# Sheet1.net
KiCad netlist of a schematic drawn in Altium Designer
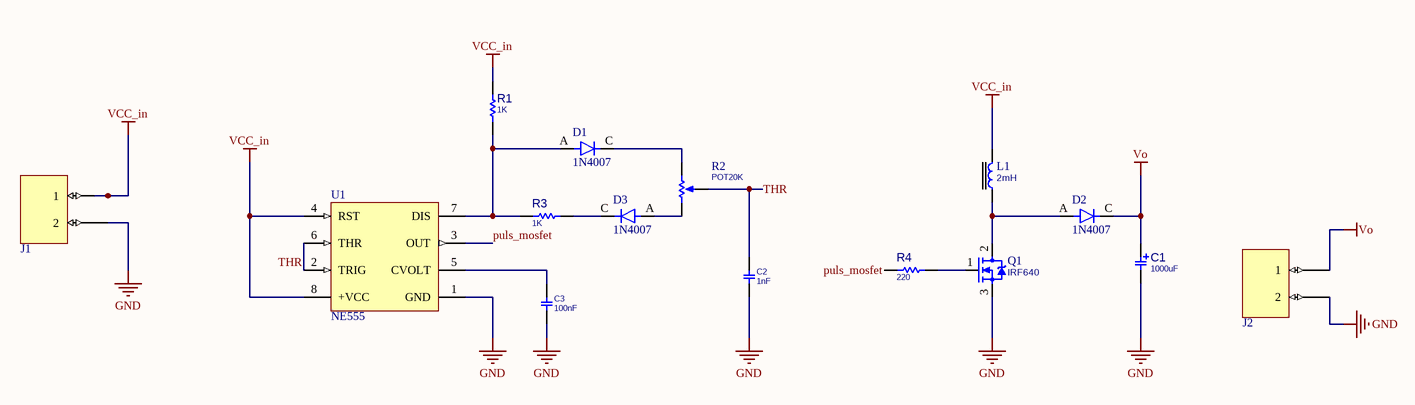
[diagram p0: Sheet1.SchDoc]

(export (version "E")
  (design (tool "Eeschema 10.0.6"))
  (components
    (comp (ref "C1")
      (value "1000uF")
      (footprint "C_EL_8X12")
      (description "CAP, THD, ELEC,")
      (fields (field (name "MANF_P#") "MANF_PART#") (field (name "MANF") "MANF"))
      (libsource (lib "passive_thd") (part "CAP_THD_EL_10X20"))
    )
    (comp (ref "C2")
      (value "1nF")
      (footprint "C_CER_D3")
      (description "CAP, THD, CER MULTI LAYER,")
      (fields (field (name "MANF_P#") "MANF_PART#") (field (name "MANF") "MANF"))
      (libsource (lib "passive_thd") (part "CAP_THD_CERML"))
    )
    (comp (ref "C3")
      (value "100nF")
      (footprint "C_CER_D3")
      (description "CAP, THD, CER MULTI LAYER,")
      (fields (field (name "MANF_P#") "MANF_PART#") (field (name "MANF") "MANF"))
      (libsource (lib "passive_thd") (part "CAP_THD_CERML"))
    )
    (comp (ref "D1")
      (value "1N4007")
      (footprint "DIOAD1060W80L520D270")
      (description "Diode Standard 1000 V 1A Through Hole DO-41")
      (fields (field (name "MF") "NTE Electronics, Inc."))
      (libsource (lib "1N4007") (part "1N4007"))
    )
    (comp (ref "D2")
      (value "1N4007")
      (footprint "DIOAD1060W80L520D270")
      (description "Diode Standard 1000 V 1A Through Hole DO-41")
      (fields (field (name "MF") "NTE Electronics, Inc."))
      (libsource (lib "1N4007") (part "1N4007"))
    )
    (comp (ref "D3")
      (value "1N4007")
      (footprint "DIOAD1060W80L520D270")
      (description "Diode Standard 1000 V 1A Through Hole DO-41")
      (fields (field (name "MF") "NTE Electronics, Inc."))
      (libsource (lib "1N4007") (part "1N4007"))
    )
    (comp (ref "J1")
      (value "con_x2")
      (footprint "TBG_2")
      (libsource (lib "My_liberary_Schematic") (part "con_x2"))
    )
    (comp (ref "J2")
      (value "con_x2")
      (footprint "TBG_2")
      (libsource (lib "My_liberary_Schematic") (part "con_x2"))
    )
    (comp (ref "L1")
      (value "2mH")
      (footprint "C_EL_10X20")
      (description "INDUCTOR, THD")
      (libsource (lib "passive_thd") (part "IND_THD"))
    )
    (comp (ref "Q1")
      (value "IRF640")
      (footprint "TO220_3")
      (description "MOSFET, N-CH, 0.15RDS, 18A, 300VDS, 2~4VGSth")
      (fields (field (name "MANF") "VISHAY, ON"))
      (libsource (lib "transistor_fet") (part "MOSN_IRF640_TO220"))
    )
    (comp (ref "R1")
      (value "1K")
      (footprint "R025W_AX04")
      (description "RESISTOR, THD")
      (fields (field (name "MANF_P#") "RK73H1ETTP4701F") (field (name "MANF") "KOA SPEER"))
      (libsource (lib "passive_thd") (part "RES_THD"))
    )
    (comp (ref "R2")
      (value "POT20K")
      (footprint "POT_7X5")
      (description "RESISTOR, THD, Potentiometer Volume")
      (libsource (lib "resistor_pot_trimmer") (part "RES_THD_POT_VOLUME"))
    )
    (comp (ref "R3")
      (value "1K")
      (footprint "R025W_AX04")
      (description "RESISTOR, THD")
      (fields (field (name "MANF_P#") "RK73H1ETTP4701F") (field (name "MANF") "KOA SPEER"))
      (libsource (lib "passive_thd") (part "RES_THD"))
    )
    (comp (ref "R4")
      (value "220")
      (footprint "R025W_AX04")
      (description "RESISTOR, THD")
      (fields (field (name "MANF_P#") "RK73H1ETTP4701F") (field (name "MANF") "KOA SPEER"))
      (libsource (lib "passive_thd") (part "RES_THD"))
    )
    (comp (ref "U1") (value "NE555") (footprint "NE555") (libsource (lib "NE555") (part "NE555")))
  )
  (nets
    (net (code "1") (name "/THR") (class "Default")
      (node (ref "C2") (pin "2") (pinfunction "2_2") (pintype "passive"))
      (node (ref "R2") (pin "2") (pinfunction "TAP_2") (pintype "passive"))
      (node (ref "U1") (pin "2") (pinfunction "TRIG_2") (pintype "input"))
      (node (ref "U1") (pin "6") (pinfunction "THR_6") (pintype "input"))
    )
    (net (code "2") (name "/puls_mosfet") (class "Default")
      (node (ref "R4") (pin "2") (pinfunction "2_2") (pintype "passive"))
      (node (ref "U1") (pin "3") (pinfunction "OUT_3") (pintype "output"))
    )
    (net (code "3") (name "GND") (class "Default")
      (node (ref "C1") (pin "2") (pinfunction "2_2") (pintype "passive"))
      (node (ref "C2") (pin "1") (pinfunction "1_1") (pintype "passive"))
      (node (ref "C3") (pin "1") (pinfunction "1_1") (pintype "passive"))
      (node (ref "J1") (pin "2") (pinfunction "2_2") (pintype "bidirectional"))
      (node (ref "J2") (pin "2") (pinfunction "2_2") (pintype "bidirectional"))
      (node (ref "Q1") (pin "3") (pinfunction "S_3") (pintype "passive"))
      (node (ref "U1") (pin "1") (pinfunction "GND_1") (pintype "power_in"))
    )
    (net (code "4") (name "Net-(D3-PadC)") (class "Default")
      (node (ref "D3") (pin "C") (pinfunction "C_C") (pintype "passive"))
      (node (ref "R3") (pin "1") (pinfunction "1_1") (pintype "passive"))
    )
    (net (code "5") (name "Net-(Q1-D)") (class "Default")
      (node (ref "D2") (pin "A") (pinfunction "A_A") (pintype "passive"))
      (node (ref "L1") (pin "1") (pinfunction "1_1") (pintype "passive"))
      (node (ref "Q1") (pin "2") (pinfunction "D_2") (pintype "passive"))
    )
    (net (code "6") (name "Net-(Q1-G)") (class "Default")
      (node (ref "Q1") (pin "1") (pinfunction "G_1") (pintype "passive"))
      (node (ref "R4") (pin "1") (pinfunction "1_1") (pintype "passive"))
    )
    (net (code "7") (name "Net-(R2-BOT)") (class "Default")
      (node (ref "D1") (pin "C") (pinfunction "C_C") (pintype "passive"))
      (node (ref "R2") (pin "3") (pinfunction "BOT_3") (pintype "passive"))
    )
    (net (code "8") (name "Net-(R2-TOP)") (class "Default")
      (node (ref "D3") (pin "A") (pinfunction "A_A") (pintype "passive"))
      (node (ref "R2") (pin "1") (pinfunction "TOP_1") (pintype "passive"))
    )
    (net (code "9") (name "Net-(U1-CVOLT)") (class "Default")
      (node (ref "C3") (pin "2") (pinfunction "2_2") (pintype "passive"))
      (node (ref "U1") (pin "5") (pinfunction "CVOLT_5") (pintype "passive"))
    )
    (net (code "10") (name "Net-(U1-DIS)") (class "Default")
      (node (ref "D1") (pin "A") (pinfunction "A_A") (pintype "passive"))
      (node (ref "R1") (pin "1") (pinfunction "1_1") (pintype "passive"))
      (node (ref "R3") (pin "2") (pinfunction "2_2") (pintype "passive"))
      (node (ref "U1") (pin "7") (pinfunction "DIS_7") (pintype "open_collector"))
    )
    (net (code "11") (name "VCC_in") (class "Default")
      (node (ref "J1") (pin "1") (pinfunction "1_1") (pintype "bidirectional"))
      (node (ref "L1") (pin "2") (pinfunction "2_2") (pintype "passive"))
      (node (ref "R1") (pin "2") (pinfunction "2_2") (pintype "passive"))
      (node (ref "U1") (pin "4") (pinfunction "RST_4") (pintype "input"))
      (node (ref "U1") (pin "8") (pinfunction "+VCC_8") (pintype "power_in"))
    )
    (net (code "12") (name "Vo") (class "Default")
      (node (ref "C1") (pin "1") (pinfunction "1_1") (pintype "passive"))
      (node (ref "D2") (pin "C") (pinfunction "C_C") (pintype "passive"))
      (node (ref "J2") (pin "1") (pinfunction "1_1") (pintype "bidirectional"))
    )
  )
)
